# GSM.net
KiCad netlist of a schematic drawn in Altium Designer
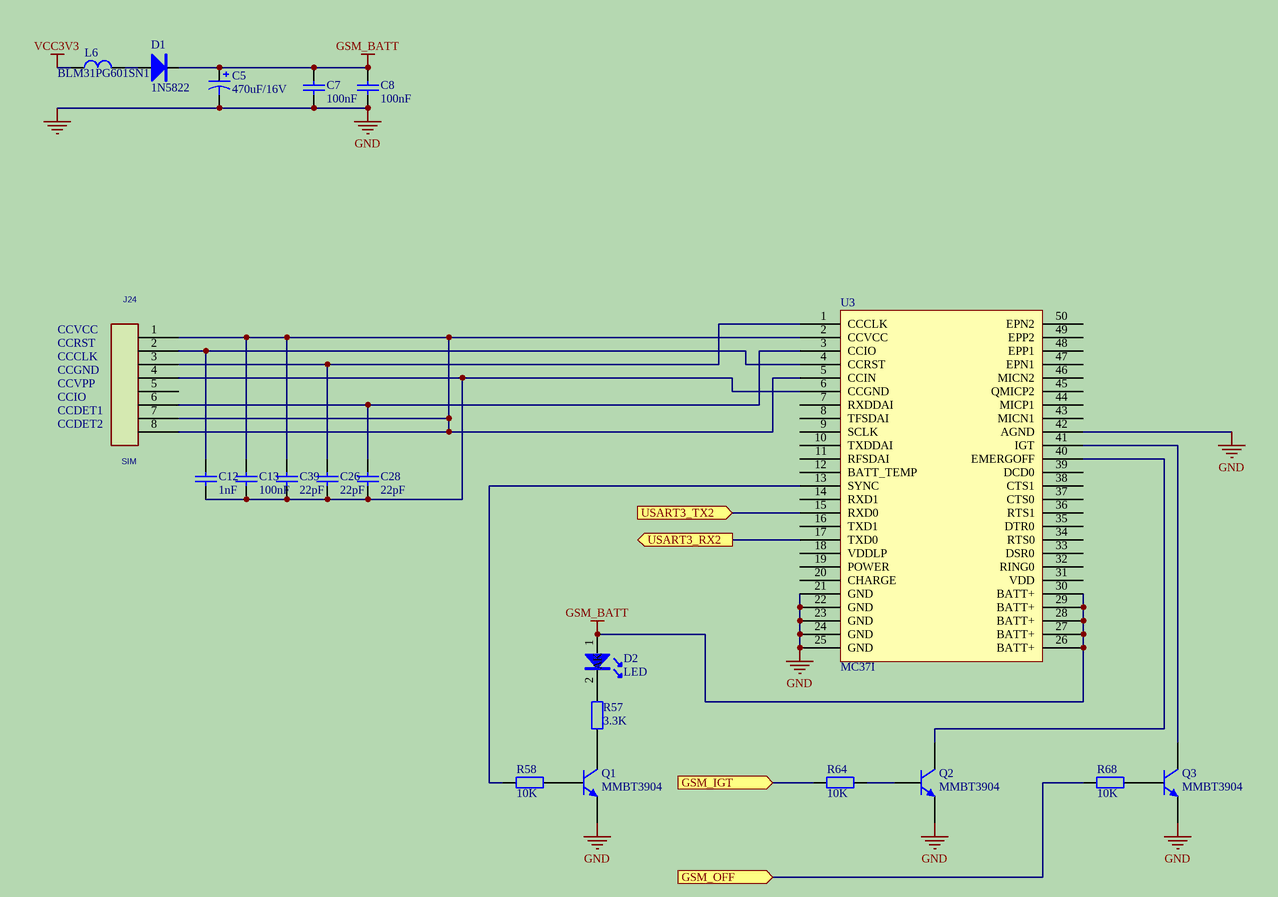
[diagram p0: GSM.SchDoc]

(export (version "E")
  (design (tool "Eeschema 10.0.6"))
  (components
    (comp (ref "C5")
      (value "470uF/16V")
      (footprint "CD2/3")
      (description "Polarized Capacitor (Radial)")
      (fields (field (name "PUBLISHER") "Altium Limited"))
      (libsource (lib "Miscellaneous Devices") (part "Cap Pol1"))
    )
    (comp (ref "C7")
      (value "100nF")
      (footprint "贴片元器件:C0805")
      (description "Capacitor")
      (fields (field (name "PUBLISHER") "Altium Limited"))
      (libsource (lib "Miscellaneous Devices") (part "Cap"))
    )
    (comp (ref "C8")
      (value "100nF")
      (footprint "贴片元器件:C0805")
      (description "Capacitor")
      (fields (field (name "PUBLISHER") "Altium Limited"))
      (libsource (lib "Miscellaneous Devices") (part "Cap"))
    )
    (comp (ref "C12")
      (value "1nF")
      (footprint "贴片元器件:C0805")
      (description "Capacitor")
      (fields (field (name "PUBLISHER") "Altium Limited"))
      (libsource (lib "Miscellaneous Devices") (part "Cap"))
    )
    (comp (ref "C13")
      (value "100nF")
      (footprint "贴片元器件:C0805")
      (description "Capacitor")
      (fields (field (name "PUBLISHER") "Altium Limited"))
      (libsource (lib "Miscellaneous Devices") (part "Cap"))
    )
    (comp (ref "C26")
      (value "22pF")
      (footprint "贴片元器件:C0805")
      (description "Capacitor")
      (fields (field (name "PUBLISHER") "Altium Limited"))
      (libsource (lib "Miscellaneous Devices") (part "Cap"))
    )
    (comp (ref "C28")
      (value "22pF")
      (footprint "贴片元器件:C0805")
      (description "Capacitor")
      (fields (field (name "PUBLISHER") "Altium Limited"))
      (libsource (lib "Miscellaneous Devices") (part "Cap"))
    )
    (comp (ref "C39")
      (value "22pF")
      (footprint "贴片元器件:C0805")
      (description "Capacitor")
      (fields (field (name "PUBLISHER") "Altium Limited"))
      (libsource (lib "Miscellaneous Devices") (part "Cap"))
    )
    (comp (ref "D1")
      (value "1N5822")
      (footprint "V5")
      (description "Diode")
      (libsource (lib "Devices") (part "2JG"))
    )
    (comp (ref "D2") (value "LED") (footprint "LED0805") (libsource (lib "Devices") (part "LED")))
    (comp (ref "J24") (value "SIM") (libsource (lib "*") (part "CON8")))
    (comp (ref "L6") (value "BLM31PG601SN1") (footprint "L1206") (libsource (lib "Devices") (part "L1")))
    (comp (ref "Q1")
      (value "MMBT3904")
      (footprint "SOT23_N")
      (description "NPN Switching Transistor")
      (fields (field (name "PUBLISHER") "Altium Limited"))
      (libsource (lib "Philips Discrete BJT - Low Power") (part "MMBT3904"))
    )
    (comp (ref "Q2")
      (value "MMBT3904")
      (footprint "SOT23_N")
      (description "NPN Switching Transistor")
      (fields (field (name "PUBLISHER") "Altium Limited"))
      (libsource (lib "Philips Discrete BJT - Low Power") (part "MMBT3904"))
    )
    (comp (ref "Q3")
      (value "MMBT3904")
      (footprint "SOT23_N")
      (description "NPN Switching Transistor")
      (fields (field (name "PUBLISHER") "Altium Limited"))
      (libsource (lib "Philips Discrete BJT - Low Power") (part "MMBT3904"))
    )
    (comp (ref "R57")
      (value "3.3K")
      (footprint "R0805")
      (description "Resistor")
      (fields (field (name "PUBLISHER") "Altium Limited"))
      (libsource (lib "Miscellaneous Devices") (part "Res2"))
    )
    (comp (ref "R58")
      (value "10K")
      (footprint "R0805")
      (description "Resistor")
      (fields (field (name "PUBLISHER") "Altium Limited"))
      (libsource (lib "") (part "Res2_1"))
    )
    (comp (ref "R64")
      (value "10K")
      (footprint "R0805")
      (description "Resistor")
      (fields (field (name "PUBLISHER") "Altium Limited"))
      (libsource (lib "") (part "Res2_1"))
    )
    (comp (ref "R68")
      (value "10K")
      (footprint "R0805")
      (description "Resistor")
      (fields (field (name "PUBLISHER") "Altium Limited"))
      (libsource (lib "") (part "Res2_1"))
    )
    (comp (ref "U3") (value "MC37I") (footprint "MC37I") (libsource (lib "IC") (part "MC37I")))
  )
  (nets
    (net (code "1") (name "/GSM_IGT") (class "Default")
      (node (ref "R64") (pin "1") (pinfunction "1_1") (pintype "passive"))
    )
    (net (code "2") (name "/GSM_OFF") (class "Default")
      (node (ref "R68") (pin "1") (pinfunction "1_1") (pintype "passive"))
    )
    (net (code "3") (name "/USART3_RX2") (class "Default")
      (node (ref "U3") (pin "17") (pinfunction "TXD0_17") (pintype "passive"))
    )
    (net (code "4") (name "/USART3_TX2") (class "Default")
      (node (ref "U3") (pin "15") (pinfunction "RXD0_15") (pintype "passive"))
    )
    (net (code "5") (name "GND") (class "Default")
      (node (ref "C5") (pin "2") (pinfunction "2_2") (pintype "passive"))
      (node (ref "C7") (pin "1") (pinfunction "1_1") (pintype "passive"))
      (node (ref "C8") (pin "1") (pinfunction "1_1") (pintype "passive"))
      (node (ref "Q1") (pin "2") (pinfunction "E_2") (pintype "passive"))
      (node (ref "Q2") (pin "2") (pinfunction "E_2") (pintype "passive"))
      (node (ref "Q3") (pin "2") (pinfunction "E_2") (pintype "passive"))
      (node (ref "U3") (pin "21") (pinfunction "GND_21") (pintype "passive"))
      (node (ref "U3") (pin "22") (pinfunction "GND_22") (pintype "passive"))
      (node (ref "U3") (pin "23") (pinfunction "GND_23") (pintype "passive"))
      (node (ref "U3") (pin "24") (pinfunction "GND_24") (pintype "passive"))
      (node (ref "U3") (pin "25") (pinfunction "GND_25") (pintype "passive"))
      (node (ref "U3") (pin "42") (pinfunction "AGND_42") (pintype "passive"))
    )
    (net (code "6") (name "GSM_BATT") (class "Default")
      (node (ref "C5") (pin "1") (pinfunction "1_1") (pintype "passive"))
      (node (ref "C7") (pin "2") (pinfunction "2_2") (pintype "passive"))
      (node (ref "C8") (pin "2") (pinfunction "2_2") (pintype "passive"))
      (node (ref "D1") (pin "2") (pinfunction "K_2") (pintype "passive"))
      (node (ref "D2") (pin "1") (pinfunction "A_1") (pintype "passive"))
      (node (ref "U3") (pin "26") (pinfunction "BATT+_26") (pintype "passive"))
      (node (ref "U3") (pin "27") (pinfunction "BATT+_27") (pintype "passive"))
      (node (ref "U3") (pin "28") (pinfunction "BATT+_28") (pintype "passive"))
      (node (ref "U3") (pin "29") (pinfunction "BATT+_29") (pintype "passive"))
      (node (ref "U3") (pin "30") (pinfunction "BATT+_30") (pintype "passive"))
    )
    (net (code "7") (name "Net-(D1-A)") (class "Default")
      (node (ref "D1") (pin "1") (pinfunction "A_1") (pintype "passive"))
      (node (ref "L6") (pin "2") (pinfunction "2_2") (pintype "passive"))
    )
    (net (code "8") (name "Net-(D2-K)") (class "Default")
      (node (ref "D2") (pin "2") (pinfunction "K_2") (pintype "passive"))
      (node (ref "R57") (pin "2") (pinfunction "2_2") (pintype "passive"))
    )
    (net (code "9") (name "Net-(Q1-B)") (class "Default")
      (node (ref "Q1") (pin "1") (pinfunction "B_1") (pintype "passive"))
      (node (ref "R58") (pin "2") (pinfunction "2_2") (pintype "passive"))
    )
    (net (code "10") (name "Net-(Q1-C)") (class "Default")
      (node (ref "Q1") (pin "3") (pinfunction "C_3") (pintype "passive"))
      (node (ref "R57") (pin "1") (pinfunction "1_1") (pintype "passive"))
    )
    (net (code "11") (name "Net-(Q2-B)") (class "Default")
      (node (ref "Q2") (pin "1") (pinfunction "B_1") (pintype "passive"))
      (node (ref "R64") (pin "2") (pinfunction "2_2") (pintype "passive"))
    )
    (net (code "12") (name "Net-(Q2-C)") (class "Default")
      (node (ref "Q2") (pin "3") (pinfunction "C_3") (pintype "passive"))
      (node (ref "U3") (pin "40") (pinfunction "EMERGOFF_40") (pintype "passive"))
    )
    (net (code "13") (name "Net-(Q3-B)") (class "Default")
      (node (ref "Q3") (pin "1") (pinfunction "B_1") (pintype "passive"))
      (node (ref "R68") (pin "2") (pinfunction "2_2") (pintype "passive"))
    )
    (net (code "14") (name "Net-(Q3-C)") (class "Default")
      (node (ref "Q3") (pin "3") (pinfunction "C_3") (pintype "passive"))
      (node (ref "U3") (pin "41") (pinfunction "IGT_41") (pintype "passive"))
    )
    (net (code "15") (name "Net-(U3-CCCLK)") (class "Default")
      (node (ref "C26") (pin "2") (pinfunction "2_2") (pintype "passive"))
      (node (ref "J24") (pin "3") (pinfunction "3_3") (pintype "passive"))
      (node (ref "U3") (pin "1") (pinfunction "CCCLK_1") (pintype "passive"))
    )
    (net (code "16") (name "Net-(U3-CCGND)") (class "Default")
      (node (ref "C12") (pin "1") (pinfunction "1_1") (pintype "passive"))
      (node (ref "C13") (pin "1") (pinfunction "1_1") (pintype "passive"))
      (node (ref "C26") (pin "1") (pinfunction "1_1") (pintype "passive"))
      (node (ref "C28") (pin "1") (pinfunction "1_1") (pintype "passive"))
      (node (ref "C39") (pin "1") (pinfunction "1_1") (pintype "passive"))
      (node (ref "J24") (pin "4") (pinfunction "4_4") (pintype "passive"))
      (node (ref "U3") (pin "6") (pinfunction "CCGND_6") (pintype "passive"))
    )
    (net (code "17") (name "Net-(U3-CCIN)") (class "Default")
      (node (ref "C13") (pin "2") (pinfunction "2_2") (pintype "passive"))
      (node (ref "C39") (pin "2") (pinfunction "2_2") (pintype "passive"))
      (node (ref "J24") (pin "1") (pinfunction "1_1") (pintype "passive"))
      (node (ref "J24") (pin "7") (pinfunction "7_7") (pintype "passive"))
      (node (ref "J24") (pin "8") (pinfunction "8_8") (pintype "passive"))
      (node (ref "U3") (pin "2") (pinfunction "CCVCC_2") (pintype "passive"))
      (node (ref "U3") (pin "5") (pinfunction "CCIN_5") (pintype "passive"))
    )
    (net (code "18") (name "Net-(U3-CCIO)") (class "Default")
      (node (ref "C28") (pin "2") (pinfunction "2_2") (pintype "passive"))
      (node (ref "J24") (pin "6") (pinfunction "6_6") (pintype "passive"))
      (node (ref "U3") (pin "3") (pinfunction "CCIO_3") (pintype "passive"))
    )
    (net (code "19") (name "Net-(U3-CCRST)") (class "Default")
      (node (ref "C12") (pin "2") (pinfunction "2_2") (pintype "passive"))
      (node (ref "J24") (pin "2") (pinfunction "2_2") (pintype "passive"))
      (node (ref "U3") (pin "4") (pinfunction "CCRST_4") (pintype "passive"))
    )
    (net (code "20") (name "Net-(U3-SYNC)") (class "Default")
      (node (ref "R58") (pin "1") (pinfunction "1_1") (pintype "passive"))
      (node (ref "U3") (pin "13") (pinfunction "SYNC_13") (pintype "passive"))
    )
    (net (code "21") (name "VCC3V3") (class "Default")
      (node (ref "L6") (pin "1") (pinfunction "1_1") (pintype "passive"))
    )
    (net (code "22") (name "unconnected-(J24-Pad5)") (class "Default")
      (node (ref "J24") (pin "5") (pinfunction "5_5") (pintype "passive"))
    )
    (net (code "23") (name "unconnected-(U3-BATT_TEMP-Pad12)") (class "Default")
      (node (ref "U3") (pin "12") (pinfunction "BATT_TEMP_12") (pintype "passive"))
    )
    (net (code "24") (name "unconnected-(U3-CHARGE-Pad20)") (class "Default")
      (node (ref "U3") (pin "20") (pinfunction "CHARGE_20") (pintype "passive"))
    )
    (net (code "25") (name "unconnected-(U3-CTS0-Pad37)") (class "Default")
      (node (ref "U3") (pin "37") (pinfunction "CTS0_37") (pintype "passive"))
    )
    (net (code "26") (name "unconnected-(U3-CTS1-Pad38)") (class "Default")
      (node (ref "U3") (pin "38") (pinfunction "CTS1_38") (pintype "passive"))
    )
    (net (code "27") (name "unconnected-(U3-DCD0-Pad39)") (class "Default")
      (node (ref "U3") (pin "39") (pinfunction "DCD0_39") (pintype "passive"))
    )
    (net (code "28") (name "unconnected-(U3-DSR0-Pad33)") (class "Default")
      (node (ref "U3") (pin "33") (pinfunction "DSR0_33") (pintype "passive"))
    )
    (net (code "29") (name "unconnected-(U3-DTR0-Pad35)") (class "Default")
      (node (ref "U3") (pin "35") (pinfunction "DTR0_35") (pintype "passive"))
    )
    (net (code "30") (name "unconnected-(U3-EPN1-Pad47)") (class "Default")
      (node (ref "U3") (pin "47") (pinfunction "EPN1_47") (pintype "passive"))
    )
    (net (code "31") (name "unconnected-(U3-EPN2-Pad50)") (class "Default")
      (node (ref "U3") (pin "50") (pinfunction "EPN2_50") (pintype "passive"))
    )
    (net (code "32") (name "unconnected-(U3-EPP1-Pad48)") (class "Default")
      (node (ref "U3") (pin "48") (pinfunction "EPP1_48") (pintype "passive"))
    )
    (net (code "33") (name "unconnected-(U3-EPP2-Pad49)") (class "Default")
      (node (ref "U3") (pin "49") (pinfunction "EPP2_49") (pintype "passive"))
    )
    (net (code "34") (name "unconnected-(U3-MICN1-Pad43)") (class "Default")
      (node (ref "U3") (pin "43") (pinfunction "MICN1_43") (pintype "passive"))
    )
    (net (code "35") (name "unconnected-(U3-MICN2-Pad46)") (class "Default")
      (node (ref "U3") (pin "46") (pinfunction "MICN2_46") (pintype "passive"))
    )
    (net (code "36") (name "unconnected-(U3-MICP1-Pad44)") (class "Default")
      (node (ref "U3") (pin "44") (pinfunction "MICP1_44") (pintype "passive"))
    )
    (net (code "37") (name "unconnected-(U3-POWER-Pad19)") (class "Default")
      (node (ref "U3") (pin "19") (pinfunction "POWER_19") (pintype "passive"))
    )
    (net (code "38") (name "unconnected-(U3-QMICP2-Pad45)") (class "Default")
      (node (ref "U3") (pin "45") (pinfunction "QMICP2_45") (pintype "passive"))
    )
    (net (code "39") (name "unconnected-(U3-RFSDAI-Pad11)") (class "Default")
      (node (ref "U3") (pin "11") (pinfunction "RFSDAI_11") (pintype "passive"))
    )
    (net (code "40") (name "unconnected-(U3-RING0-Pad32)") (class "Default")
      (node (ref "U3") (pin "32") (pinfunction "RING0_32") (pintype "passive"))
    )
    (net (code "41") (name "unconnected-(U3-RTS0-Pad34)") (class "Default")
      (node (ref "U3") (pin "34") (pinfunction "RTS0_34") (pintype "passive"))
    )
    (net (code "42") (name "unconnected-(U3-RTS1-Pad36)") (class "Default")
      (node (ref "U3") (pin "36") (pinfunction "RTS1_36") (pintype "passive"))
    )
    (net (code "43") (name "unconnected-(U3-RXD1-Pad14)") (class "Default")
      (node (ref "U3") (pin "14") (pinfunction "RXD1_14") (pintype "passive"))
    )
    (net (code "44") (name "unconnected-(U3-RXDDAI-Pad7)") (class "Default")
      (node (ref "U3") (pin "7") (pinfunction "RXDDAI_7") (pintype "passive"))
    )
    (net (code "45") (name "unconnected-(U3-SCLK-Pad9)") (class "Default")
      (node (ref "U3") (pin "9") (pinfunction "SCLK_9") (pintype "passive"))
    )
    (net (code "46") (name "unconnected-(U3-TFSDAI-Pad8)") (class "Default")
      (node (ref "U3") (pin "8") (pinfunction "TFSDAI_8") (pintype "passive"))
    )
    (net (code "47") (name "unconnected-(U3-TXD1-Pad16)") (class "Default")
      (node (ref "U3") (pin "16") (pinfunction "TXD1_16") (pintype "passive"))
    )
    (net (code "48") (name "unconnected-(U3-TXDDAI-Pad10)") (class "Default")
      (node (ref "U3") (pin "10") (pinfunction "TXDDAI_10") (pintype "passive"))
    )
    (net (code "49") (name "unconnected-(U3-VDD-Pad31)") (class "Default")
      (node (ref "U3") (pin "31") (pinfunction "VDD_31") (pintype "passive"))
    )
    (net (code "50") (name "unconnected-(U3-VDDLP-Pad18)") (class "Default")
      (node (ref "U3") (pin "18") (pinfunction "VDDLP_18") (pintype "passive"))
    )
  )
)
